# hybrid_lower_pcb3.net
KiCad netlist of a schematic drawn in EAGLE
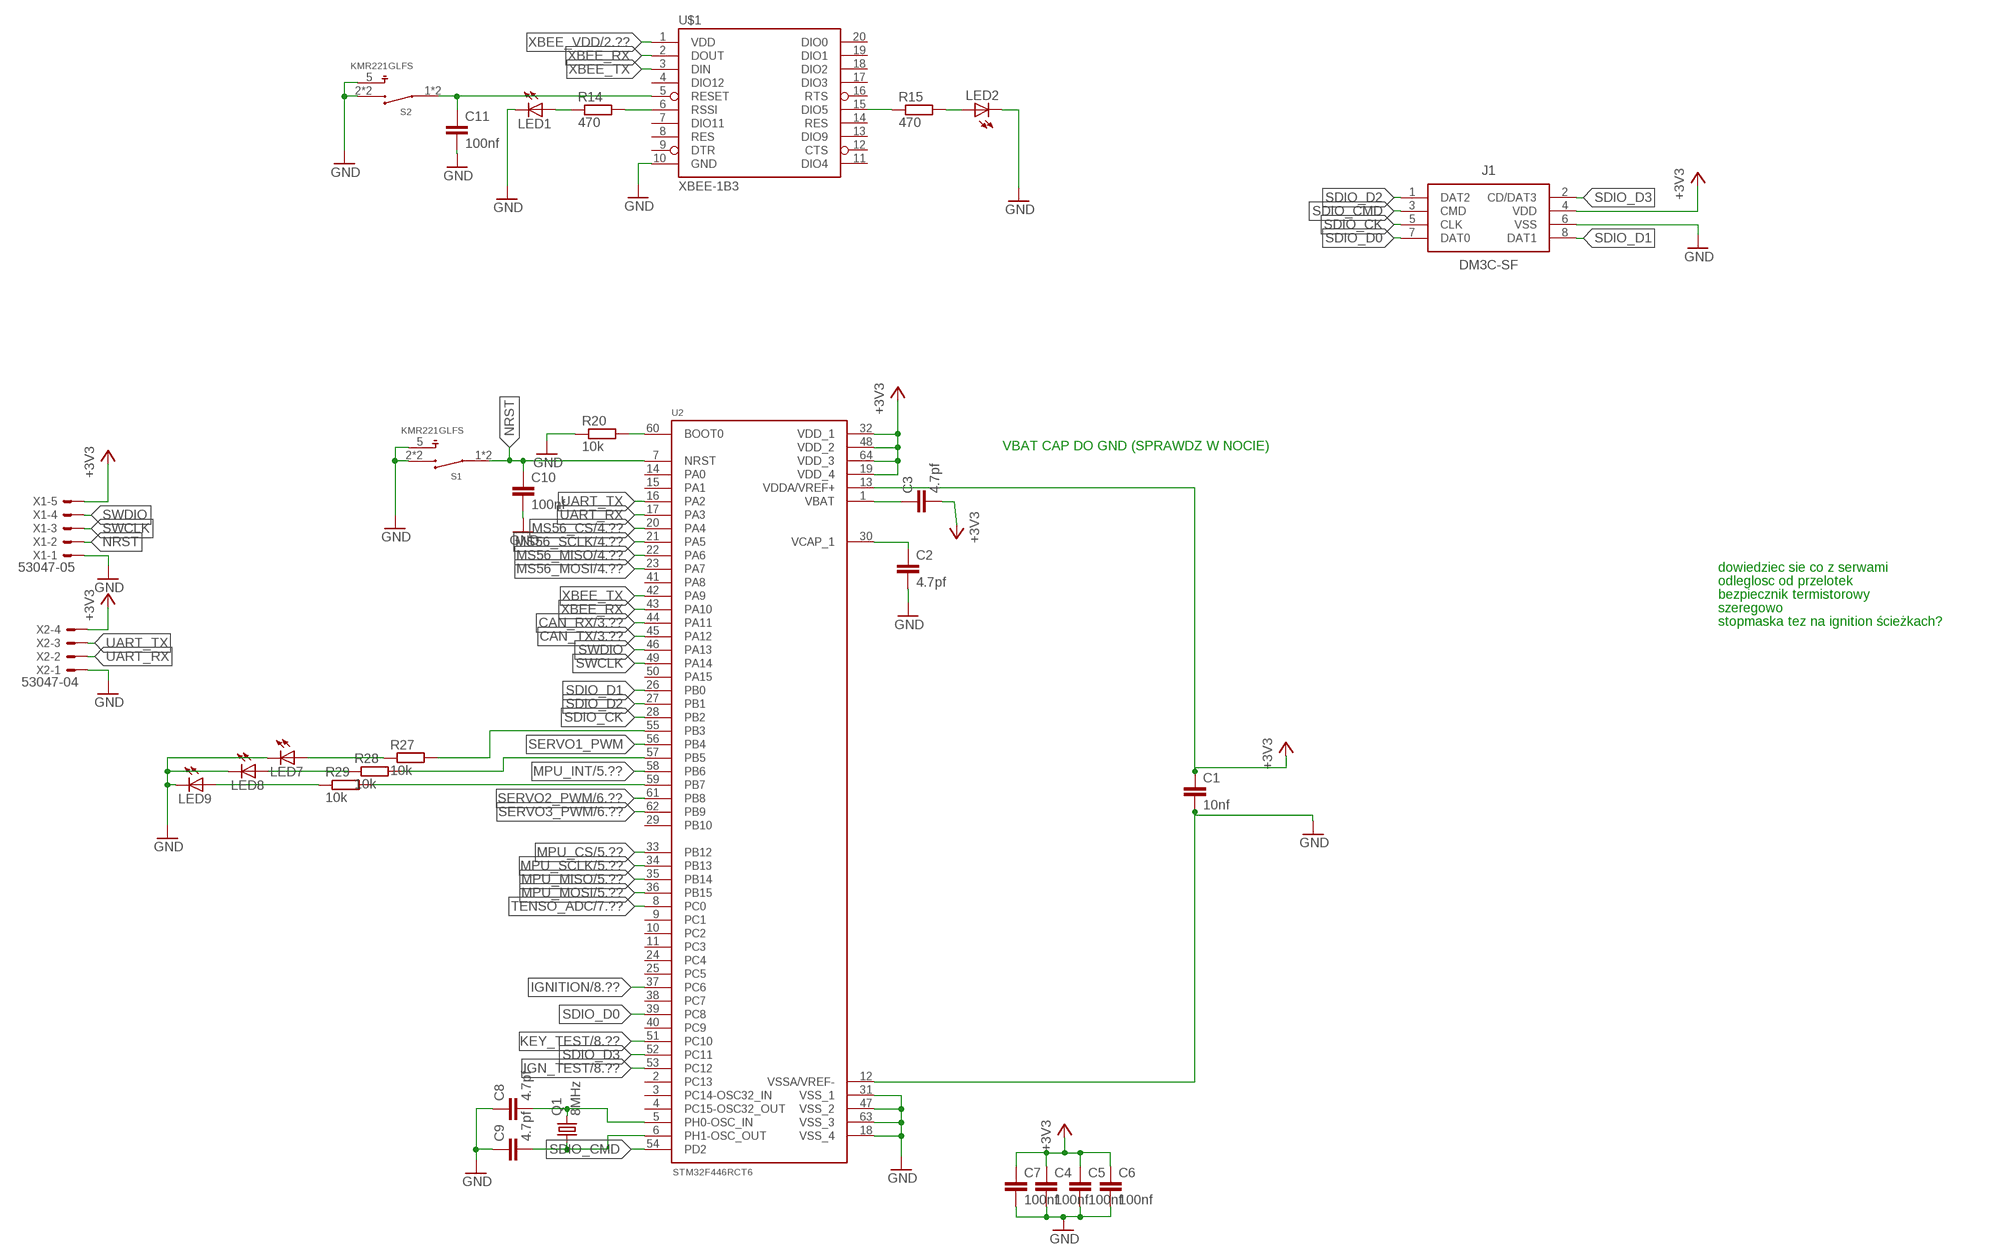
[diagram p0: schematic, sheet 1]
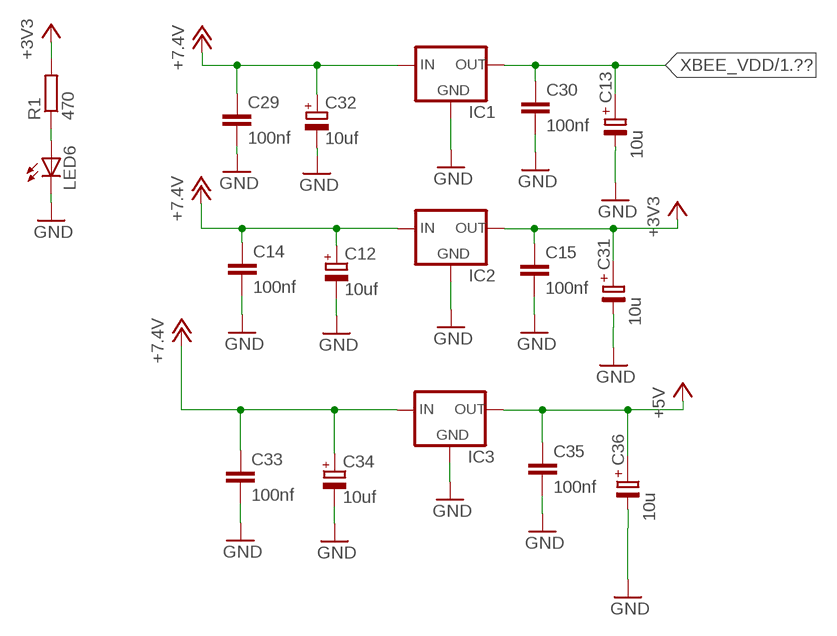
[diagram p1: schematic, sheet 2]
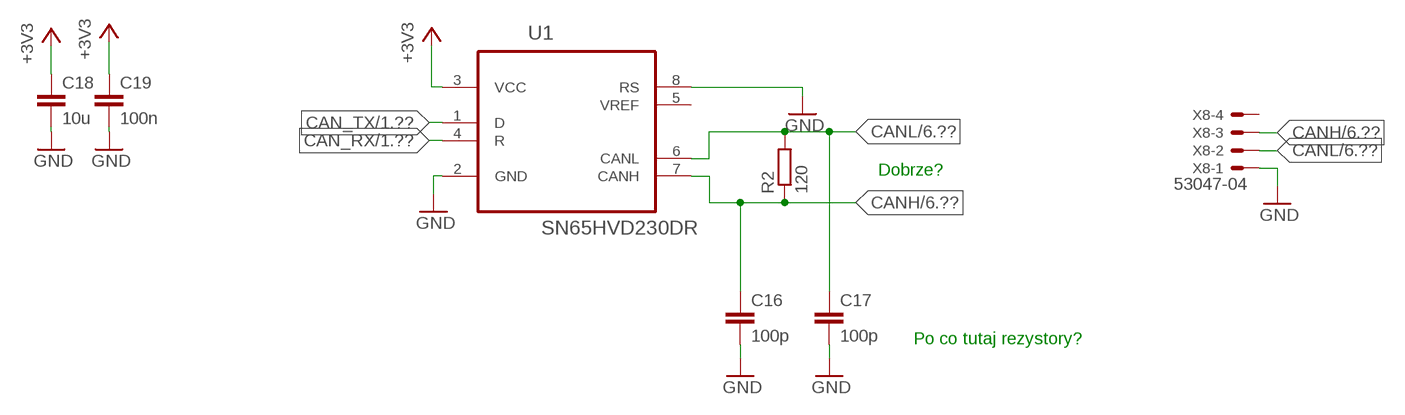
[diagram p2: schematic, sheet 3]
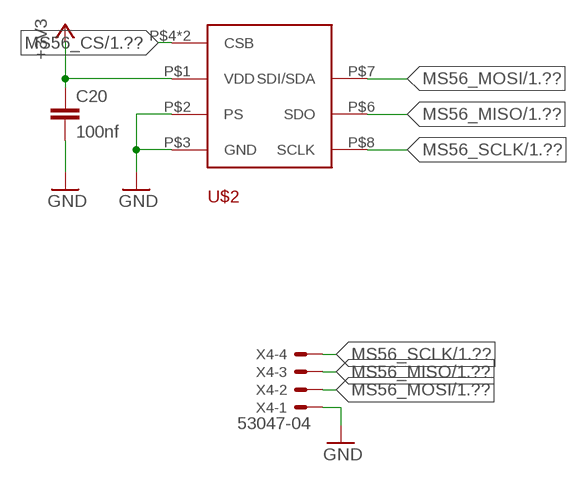
[diagram p3: schematic, sheet 4]
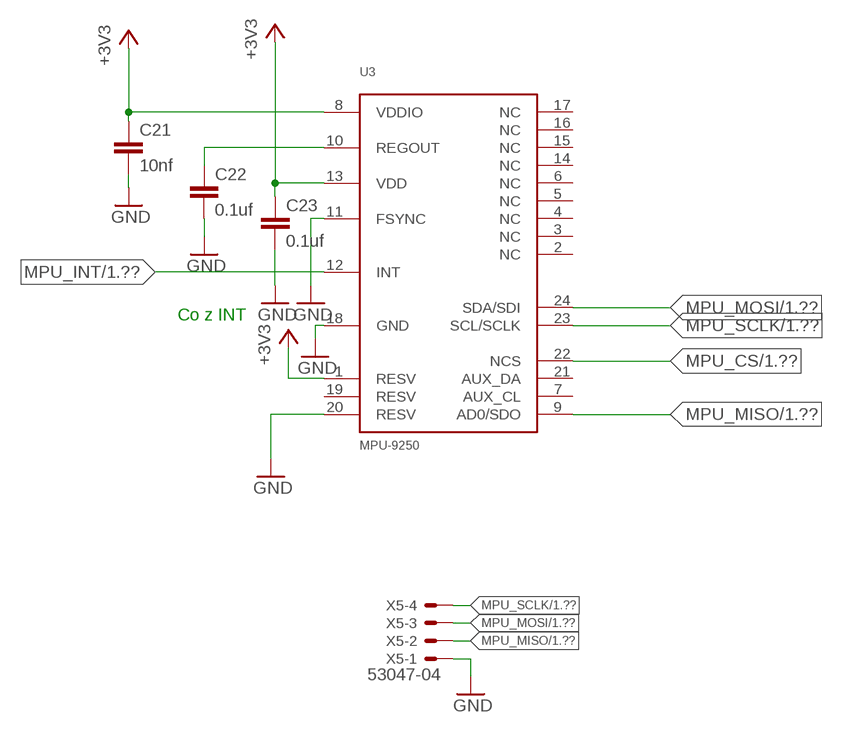
[diagram p4: schematic, sheet 5]
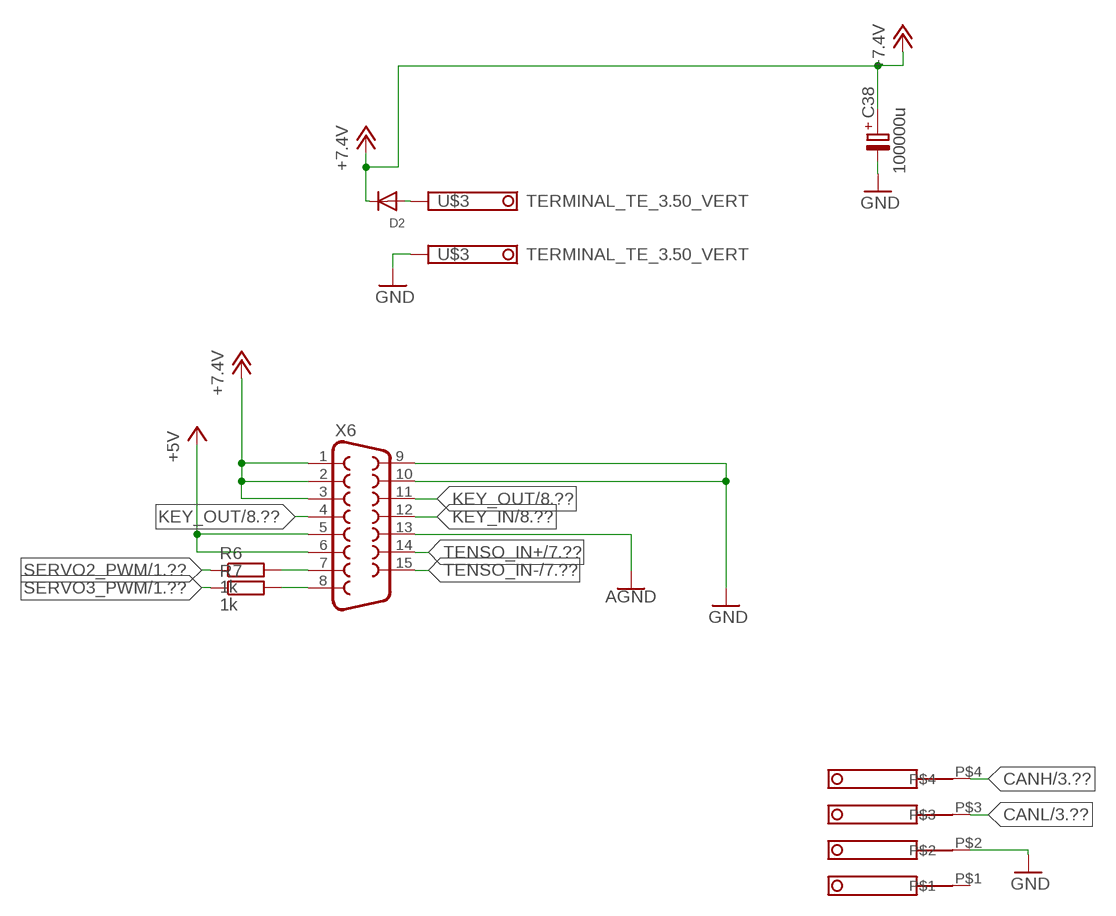
[diagram p5: schematic, sheet 6]
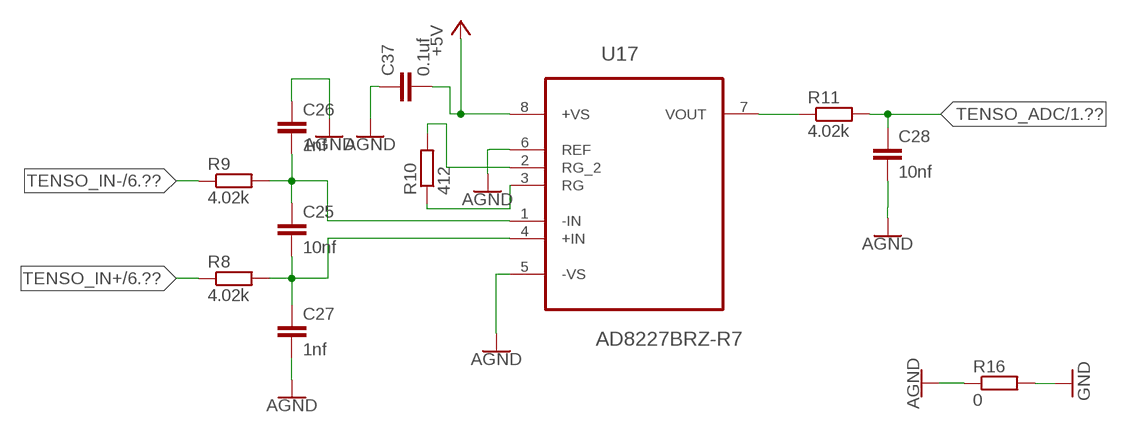
[diagram p6: schematic, sheet 7]
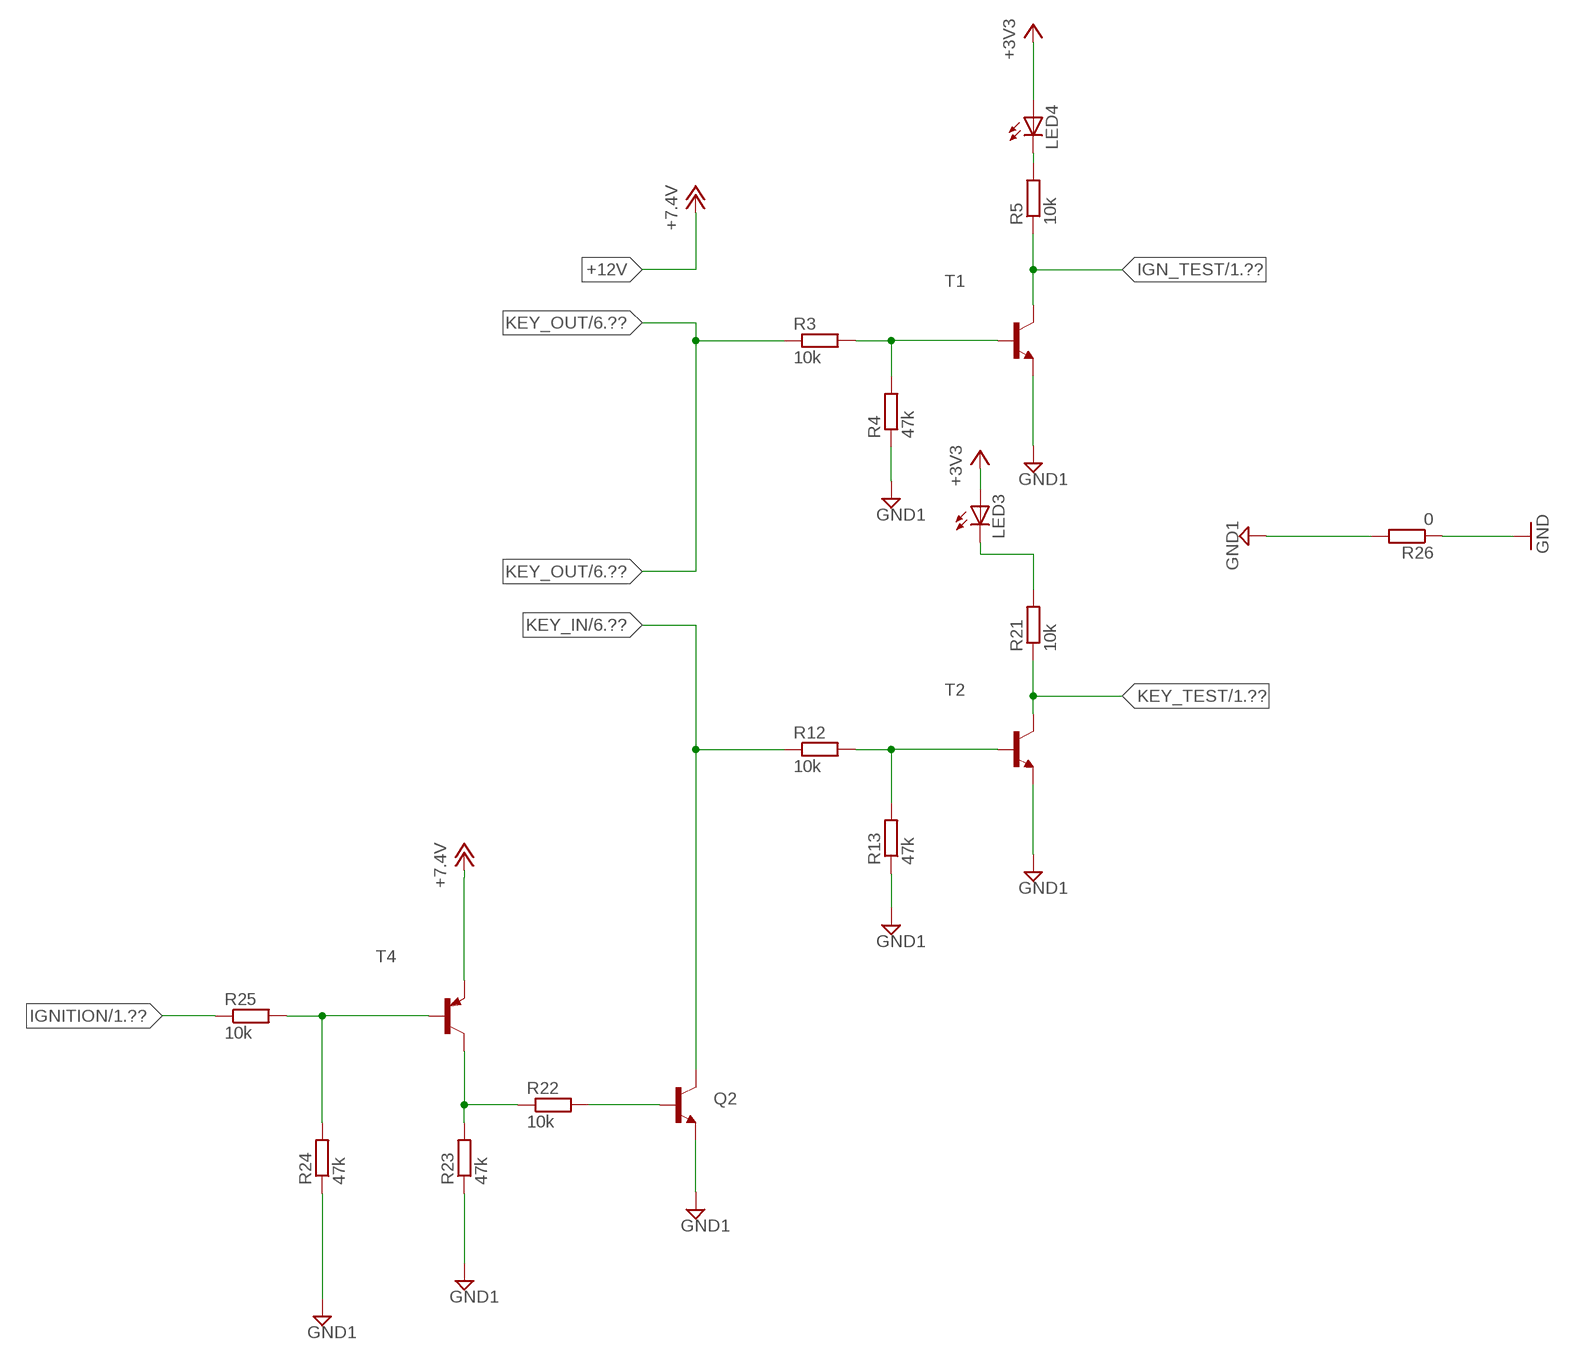
[diagram p7: schematic, sheet 8]

(export (version "E")
  (design (tool "Eeschema 10.0.6"))
  (components
    (comp (ref "C16")
      (value "100p")
      (footprint "eagle-import:C0603")
      (libsource (lib "eagle-import") (part "C-EUC0603"))
    )
    (comp (ref "C17")
      (value "100p")
      (footprint "eagle-import:C0603")
      (libsource (lib "eagle-import") (part "C-EUC0603"))
    )
    (comp (ref "C18")
      (value "10u")
      (footprint "eagle-import:C0603")
      (libsource (lib "eagle-import") (part "C-EUC0603"))
    )
    (comp (ref "C19")
      (value "100n")
      (footprint "eagle-import:C0603")
      (libsource (lib "eagle-import") (part "C-EUC0603"))
    )
    (comp (ref "R2")
      (value "120")
      (footprint "eagle-import:R0603")
      (libsource (lib "eagle-import") (part "R-EU_R0603"))
    )
    (comp (ref "U1")
      (value "SN65HVD230DR")
      (footprint "eagle-import:SOIC127P600X175-8N")
      (fields (field (name "MF") "Texas Instruments"))
      (libsource (lib "eagle-import") (part "SN65HVD230DR"))
    )
    (comp (ref "X8")
      (value "53047-04")
      (footprint "eagle-import:53047-04")
      (fields (field (name "MF") "WALDOM/MOLEX") (field (name "MPN") "53047-0410"))
      (libsource (lib "eagle-import") (part "53?-04047"))
    )
    (comp (ref "C12")
      (value "10uf")
      (footprint "eagle-import:SANYO-OSCON_SMD_B6")
      (libsource (lib "eagle-import") (part "CPOL-EUSANYO_SMD_B6"))
    )
    (comp (ref "C13")
      (value "10u")
      (footprint "eagle-import:TE-B-3528")
      (libsource (lib "eagle-import") (part "C-PR-SMD-TE-B"))
    )
    (comp (ref "C14")
      (value "100nf")
      (footprint "eagle-import:C0603")
      (libsource (lib "eagle-import") (part "C-EUC0603"))
    )
    (comp (ref "C15")
      (value "100nf")
      (footprint "eagle-import:C0603")
      (libsource (lib "eagle-import") (part "C-EUC0603"))
    )
    (comp (ref "C29")
      (value "100nf")
      (footprint "eagle-import:C0603")
      (libsource (lib "eagle-import") (part "C-EUC0603"))
    )
    (comp (ref "C30")
      (value "100nf")
      (footprint "eagle-import:C0603")
      (libsource (lib "eagle-import") (part "C-EUC0603"))
    )
    (comp (ref "C31")
      (value "10u")
      (footprint "eagle-import:TE-B-3528")
      (libsource (lib "eagle-import") (part "C-PR-SMD-TE-B"))
    )
    (comp (ref "C32")
      (value "10uf")
      (footprint "eagle-import:SANYO-OSCON_SMD_B6")
      (libsource (lib "eagle-import") (part "CPOL-EUSANYO_SMD_B6"))
    )
    (comp (ref "C33")
      (value "100nf")
      (footprint "eagle-import:C0603")
      (libsource (lib "eagle-import") (part "C-EUC0603"))
    )
    (comp (ref "C34")
      (value "10uf")
      (footprint "eagle-import:SANYO-OSCON_SMD_B6")
      (libsource (lib "eagle-import") (part "CPOL-EUSANYO_SMD_B6"))
    )
    (comp (ref "C35")
      (value "100nf")
      (footprint "eagle-import:C0603")
      (libsource (lib "eagle-import") (part "C-EUC0603"))
    )
    (comp (ref "C36")
      (value "10u")
      (footprint "eagle-import:TE-B-3528")
      (libsource (lib "eagle-import") (part "C-PR-SMD-TE-B"))
    )
    (comp (ref "IC1")
      (value "LM1117")
      (footprint "eagle-import:SOT223")
      (libsource (lib "eagle-import") (part "LM1117"))
    )
    (comp (ref "IC2")
      (value "LM1117")
      (footprint "eagle-import:SOT223")
      (libsource (lib "eagle-import") (part "LM1117"))
    )
    (comp (ref "IC3")
      (value "LM1117")
      (footprint "eagle-import:SOT223")
      (libsource (lib "eagle-import") (part "LM1117"))
    )
    (comp (ref "LED6")
      (value "LED0603")
      (footprint "eagle-import:LED-0603")
      (libsource (lib "eagle-import") (part "LED0603"))
    )
    (comp (ref "R1")
      (value "470")
      (footprint "eagle-import:R0603")
      (libsource (lib "eagle-import") (part "resistor_348_R-EU_R0603"))
    )
    (comp (ref "C1")
      (value "10nf")
      (footprint "eagle-import:C0603")
      (libsource (lib "eagle-import") (part "C-EUC0603"))
    )
    (comp (ref "C2")
      (value "4.7pf")
      (footprint "eagle-import:C0603")
      (libsource (lib "eagle-import") (part "C-EUC0603"))
    )
    (comp (ref "C3")
      (value "4.7pf")
      (footprint "eagle-import:C0603")
      (libsource (lib "eagle-import") (part "C-EUC0603"))
    )
    (comp (ref "C4")
      (value "100nf")
      (footprint "eagle-import:C0603")
      (libsource (lib "eagle-import") (part "C-EUC0603"))
    )
    (comp (ref "C5")
      (value "100nf")
      (footprint "eagle-import:C0603")
      (libsource (lib "eagle-import") (part "C-EUC0603"))
    )
    (comp (ref "C6")
      (value "100nf")
      (footprint "eagle-import:C0603")
      (libsource (lib "eagle-import") (part "C-EUC0603"))
    )
    (comp (ref "C7")
      (value "100nf")
      (footprint "eagle-import:C0603")
      (libsource (lib "eagle-import") (part "C-EUC0603"))
    )
    (comp (ref "C8")
      (value "4.7pf")
      (footprint "eagle-import:C0603")
      (libsource (lib "eagle-import") (part "C-EUC0603"))
    )
    (comp (ref "C9")
      (value "4.7pf")
      (footprint "eagle-import:C0603")
      (libsource (lib "eagle-import") (part "C-EUC0603"))
    )
    (comp (ref "C10")
      (value "100nf")
      (footprint "eagle-import:C0603")
      (libsource (lib "eagle-import") (part "C-EUC0603"))
    )
    (comp (ref "C11")
      (value "100nf")
      (footprint "eagle-import:C0603")
      (libsource (lib "eagle-import") (part "C-EUC0603"))
    )
    (comp (ref "J1")
      (value "DM3C-SF")
      (footprint "eagle-import:DM3C-SF")
      (fields (field (name "DIGIKEY_PART_NUMBER") "HR1940TR-ND"))
      (libsource (lib "eagle-import") (part "DM3C-SF"))
    )
    (comp (ref "LED1")
      (value "LED0603")
      (footprint "eagle-import:LED-0603")
      (libsource (lib "eagle-import") (part "LED0603"))
    )
    (comp (ref "LED2")
      (value "LED0603")
      (footprint "eagle-import:LED-0603")
      (libsource (lib "eagle-import") (part "LED0603"))
    )
    (comp (ref "LED7")
      (value "LED0603")
      (footprint "eagle-import:LED-0603")
      (libsource (lib "eagle-import") (part "LED0603"))
    )
    (comp (ref "LED8")
      (value "LED0603")
      (footprint "eagle-import:LED-0603")
      (libsource (lib "eagle-import") (part "LED0603"))
    )
    (comp (ref "LED9")
      (value "LED0603")
      (footprint "eagle-import:LED-0603")
      (libsource (lib "eagle-import") (part "LED0603"))
    )
    (comp (ref "Q1")
      (value "8MHz")
      (footprint "eagle-import:CTS406")
      (libsource (lib "eagle-import") (part "CRYSTALCTS406"))
    )
    (comp (ref "R14")
      (value "470")
      (footprint "eagle-import:R0603")
      (libsource (lib "eagle-import") (part "R-EU_R0603"))
    )
    (comp (ref "R15")
      (value "470")
      (footprint "eagle-import:R0603")
      (libsource (lib "eagle-import") (part "R-EU_R0603"))
    )
    (comp (ref "R20")
      (value "10k")
      (footprint "eagle-import:R0603")
      (libsource (lib "eagle-import") (part "resistor_348_R-EU_R0603"))
    )
    (comp (ref "R27")
      (value "10k")
      (footprint "eagle-import:R0603")
      (libsource (lib "eagle-import") (part "resistor_348_R-EU_R0603"))
    )
    (comp (ref "R28")
      (value "10k")
      (footprint "eagle-import:R0603")
      (libsource (lib "eagle-import") (part "resistor_348_R-EU_R0603"))
    )
    (comp (ref "R29")
      (value "10k")
      (footprint "eagle-import:R0603")
      (libsource (lib "eagle-import") (part "resistor_348_R-EU_R0603"))
    )
    (comp (ref "S1")
      (value "KMR221GLFS")
      (footprint "eagle-import:SW_KMR221GLFS")
      (fields (field (name "MF") "C&K Components"))
      (libsource (lib "eagle-import") (part "KMR221GLFS"))
    )
    (comp (ref "S2")
      (value "KMR221GLFS")
      (footprint "eagle-import:SW_KMR221GLFS")
      (fields (field (name "MF") "C&K Components"))
      (libsource (lib "eagle-import") (part "KMR221GLFS"))
    )
    (comp (ref "U$1")
      (value "XBEE-1B3")
      (footprint "eagle-import:XBEE-SMD")
      (libsource (lib "eagle-import") (part "XBEE-1B3"))
    )
    (comp (ref "U2")
      (value "STM32F446RCT6")
      (footprint "eagle-import:QFP50P1200X1200X160-64N")
      (fields (field (name "MF") "STMicroelectronics"))
      (libsource (lib "eagle-import") (part "STM32F446RCT6"))
    )
    (comp (ref "X1")
      (value "53047-05")
      (footprint "eagle-import:53047-05")
      (fields (field (name "MF") "MOLEX") (field (name "MPN") "53047-0510"))
      (libsource (lib "eagle-import") (part "53?-05047"))
    )
    (comp (ref "X2")
      (value "53047-04")
      (footprint "eagle-import:53047-04")
      (fields (field (name "MF") "WALDOM/MOLEX") (field (name "MPN") "53047-0410"))
      (libsource (lib "eagle-import") (part "53?-04047"))
    )
    (comp (ref "C25")
      (value "10nf")
      (footprint "eagle-import:C0603")
      (libsource (lib "eagle-import") (part "C-EUC0603"))
    )
    (comp (ref "C26")
      (value "1nf")
      (footprint "eagle-import:C0603")
      (libsource (lib "eagle-import") (part "C-EUC0603"))
    )
    (comp (ref "C27")
      (value "1nf")
      (footprint "eagle-import:C0603")
      (libsource (lib "eagle-import") (part "C-EUC0603"))
    )
    (comp (ref "C28")
      (value "10nf")
      (footprint "eagle-import:C0603")
      (libsource (lib "eagle-import") (part "C-EUC0603"))
    )
    (comp (ref "C37")
      (value "0.1uf")
      (footprint "eagle-import:C0603")
      (libsource (lib "eagle-import") (part "C-EUC0603"))
    )
    (comp (ref "R8")
      (value "4.02k")
      (footprint "eagle-import:R0603")
      (libsource (lib "eagle-import") (part "R-EU_R0603"))
    )
    (comp (ref "R9")
      (value "4.02k")
      (footprint "eagle-import:R0603")
      (libsource (lib "eagle-import") (part "R-EU_R0603"))
    )
    (comp (ref "R10")
      (value "412")
      (footprint "eagle-import:R0805")
      (libsource (lib "eagle-import") (part "R-EU_R0805"))
    )
    (comp (ref "R11")
      (value "4.02k")
      (footprint "eagle-import:R0603")
      (libsource (lib "eagle-import") (part "R-EU_R0603"))
    )
    (comp (ref "R16")
      (value "0")
      (footprint "eagle-import:R0603")
      (libsource (lib "eagle-import") (part "resistor_348_R-EU_R0603"))
    )
    (comp (ref "U17")
      (value "AD8227BRZ-R7")
      (footprint "eagle-import:SOIC127P600X175-8N")
      (libsource (lib "eagle-import") (part "AD8227BRZ-R7"))
    )
    (comp (ref "C38")
      (value "100000u")
      (footprint "eagle-import:TE-B-3528")
      (libsource (lib "eagle-import") (part "C-PR-SMD-TE-B"))
    )
    (comp (ref "D2")
      (value "DIODESOD-523")
      (footprint "eagle-import:SOD-523")
      (libsource (lib "eagle-import") (part "DIODESOD-523"))
    )
    (comp (ref "R6")
      (value "1k")
      (footprint "eagle-import:R0603")
      (libsource (lib "eagle-import") (part "R-EU_R0603"))
    )
    (comp (ref "R7")
      (value "1k")
      (footprint "eagle-import:R0603")
      (libsource (lib "eagle-import") (part "R-EU_R0603"))
    )
    (comp (ref "U$3")
      (value "TERMINAL_TE_3.50_VERT")
      (footprint "eagle-import:TE_3.5_TERMINAL_VERT")
      (libsource (lib "eagle-import") (part "TERMINAL_TE_3.50_VERT"))
    )
    (comp (ref "U$10")
      (value "39505-1005")
      (footprint "eagle-import:39505-1005")
      (libsource (lib "eagle-import") (part "39505-1005"))
    )
    (comp (ref "X6")
      (value "F15VP")
      (footprint "eagle-import:F15VP")
      (libsource (lib "eagle-import") (part "F15VP"))
    )
    (comp (ref "LED3")
      (value "LED0603")
      (footprint "eagle-import:LED-0603")
      (libsource (lib "eagle-import") (part "LED0603"))
    )
    (comp (ref "LED4")
      (value "LED0603")
      (footprint "eagle-import:LED-0603")
      (libsource (lib "eagle-import") (part "LED0603"))
    )
    (comp (ref "Q2")
      (value "TRANSISTOR_NPNSOT23-3")
      (footprint "eagle-import:SOT23-3")
      (libsource (lib "eagle-import") (part "TRANSISTOR_NPNSOT23-3"))
    )
    (comp (ref "R3")
      (value "10k")
      (footprint "eagle-import:R0603")
      (libsource (lib "eagle-import") (part "R-EU_R0603"))
    )
    (comp (ref "R4")
      (value "47k")
      (footprint "eagle-import:R0603")
      (libsource (lib "eagle-import") (part "R-EU_R0603"))
    )
    (comp (ref "R5")
      (value "10k")
      (footprint "eagle-import:R0603")
      (libsource (lib "eagle-import") (part "R-EU_R0603"))
    )
    (comp (ref "R12")
      (value "10k")
      (footprint "eagle-import:R0603")
      (libsource (lib "eagle-import") (part "R-EU_R0603"))
    )
    (comp (ref "R13")
      (value "47k")
      (footprint "eagle-import:R0603")
      (libsource (lib "eagle-import") (part "R-EU_R0603"))
    )
    (comp (ref "R21")
      (value "10k")
      (footprint "eagle-import:R0603")
      (libsource (lib "eagle-import") (part "R-EU_R0603"))
    )
    (comp (ref "R22")
      (value "10k")
      (footprint "eagle-import:R0603")
      (libsource (lib "eagle-import") (part "R-EU_R0603"))
    )
    (comp (ref "R23")
      (value "47k")
      (footprint "eagle-import:R0603")
      (libsource (lib "eagle-import") (part "R-EU_R0603"))
    )
    (comp (ref "R24")
      (value "47k")
      (footprint "eagle-import:R0603")
      (libsource (lib "eagle-import") (part "R-EU_R0603"))
    )
    (comp (ref "R25")
      (value "10k")
      (footprint "eagle-import:R0603")
      (libsource (lib "eagle-import") (part "R-EU_R0603"))
    )
    (comp (ref "R26")
      (value "0")
      (footprint "eagle-import:R0603")
      (libsource (lib "eagle-import") (part "R-EU_R0603"))
    )
    (comp (ref "T1")
      (value "BCW81-NPN-SOT23-BEC")
      (footprint "eagle-import:SOT23-BEC")
      (libsource (lib "eagle-import") (part "-NPN-SOT23-BECBCW81"))
    )
    (comp (ref "T2")
      (value "BCW81-NPN-SOT23-BEC")
      (footprint "eagle-import:SOT23-BEC")
      (libsource (lib "eagle-import") (part "-NPN-SOT23-BECBCW81"))
    )
    (comp (ref "T4")
      (value "BC807-16-PNP-SOT23-BEC")
      (footprint "eagle-import:SOT23-BEC")
      (libsource (lib "eagle-import") (part "-PNP-SOT23-BECBC807-16"))
    )
    (comp (ref "C20")
      (value "100nf")
      (footprint "eagle-import:C0603")
      (libsource (lib "eagle-import") (part "resistor_348_C-EUC0603"))
    )
    (comp (ref "U$2")
      (value "MS56XX")
      (footprint "eagle-import:MS56XX")
      (libsource (lib "eagle-import") (part "MS56XX"))
    )
    (comp (ref "X4")
      (value "53047-04")
      (footprint "eagle-import:53047-04")
      (fields (field (name "MF") "WALDOM/MOLEX") (field (name "MPN") "53047-0410"))
      (libsource (lib "eagle-import") (part "53?-04047"))
    )
    (comp (ref "C21")
      (value "10nf")
      (footprint "eagle-import:C0603")
      (libsource (lib "eagle-import") (part "C-EUC0603"))
    )
    (comp (ref "C22")
      (value "0.1uf")
      (footprint "eagle-import:C0603")
      (libsource (lib "eagle-import") (part "C-EUC0603"))
    )
    (comp (ref "C23")
      (value "0.1uf")
      (footprint "eagle-import:C0603")
      (libsource (lib "eagle-import") (part "C-EUC0603"))
    )
    (comp (ref "U3")
      (value "MPU-9250")
      (footprint "eagle-import:MPU-9250")
      (fields (field (name "MF") "InvenSense"))
      (libsource (lib "eagle-import") (part "MPU-9250"))
    )
    (comp (ref "X5")
      (value "53047-04")
      (footprint "eagle-import:53047-04")
      (fields (field (name "MF") "WALDOM/MOLEX") (field (name "MPN") "53047-0410"))
      (libsource (lib "eagle-import") (part "53?-04047"))
    )
  )
  (nets
    (net (code "1") (name "+3V3") (class "Default")
      (node (ref "C1") (pin "1") (pinfunction "1_1") (pintype "passive"))
      (node (ref "C15") (pin "1") (pinfunction "1_1") (pintype "passive"))
      (node (ref "C18") (pin "1") (pinfunction "1_1") (pintype "passive"))
      (node (ref "C19") (pin "1") (pinfunction "1_1") (pintype "passive"))
      (node (ref "C20") (pin "1") (pinfunction "1_1") (pintype "passive"))
      (node (ref "C21") (pin "1") (pinfunction "1_1") (pintype "passive"))
      (node (ref "C23") (pin "1") (pinfunction "1_1") (pintype "passive"))
      (node (ref "C3") (pin "2") (pinfunction "2_2") (pintype "passive"))
      (node (ref "C31") (pin "+") (pinfunction "+_+") (pintype "passive"))
      (node (ref "C4") (pin "1") (pinfunction "1_1") (pintype "passive"))
      (node (ref "C5") (pin "1") (pinfunction "1_1") (pintype "passive"))
      (node (ref "C6") (pin "1") (pinfunction "1_1") (pintype "passive"))
      (node (ref "C7") (pin "1") (pinfunction "1_1") (pintype "passive"))
      (node (ref "IC2") (pin "2") (pinfunction "OUT_2") (pintype "passive"))
      (node (ref "J1") (pin "4") (pinfunction "VDD_4") (pintype "passive"))
      (node (ref "LED3") (pin "A") (pinfunction "A_A") (pintype "passive"))
      (node (ref "LED4") (pin "A") (pinfunction "A_A") (pintype "passive"))
      (node (ref "R1") (pin "2") (pinfunction "2_2") (pintype "passive"))
      (node (ref "U$2") (pin "P$1") (pinfunction "VDD_P$1") (pintype "bidirectional"))
      (node (ref "U1") (pin "3") (pinfunction "VCC_3") (pintype "power_in"))
      (node (ref "U2") (pin "13") (pinfunction "VDDA/VREF+_13") (pintype "power_in"))
      (node (ref "U2") (pin "19") (pinfunction "VDD_4_19") (pintype "power_in"))
      (node (ref "U2") (pin "32") (pinfunction "VDD_1_32") (pintype "power_in"))
      (node (ref "U2") (pin "48") (pinfunction "VDD_2_48") (pintype "power_in"))
      (node (ref "U2") (pin "64") (pinfunction "VDD_3_64") (pintype "power_in"))
      (node (ref "U3") (pin "1") (pinfunction "RESV_1") (pintype "bidirectional"))
      (node (ref "U3") (pin "13") (pinfunction "VDD_13") (pintype "bidirectional"))
      (node (ref "U3") (pin "8") (pinfunction "VDDIO_8") (pintype "bidirectional"))
      (node (ref "X1") (pin "5") (pinfunction "S_5") (pintype "passive"))
      (node (ref "X2") (pin "4") (pinfunction "S_4") (pintype "passive"))
    )
    (net (code "2") (name "+5V") (class "Default")
      (node (ref "C35") (pin "1") (pinfunction "1_1") (pintype "passive"))
      (node (ref "C36") (pin "+") (pinfunction "+_+") (pintype "passive"))
      (node (ref "C37") (pin "2") (pinfunction "2_2") (pintype "passive"))
      (node (ref "IC3") (pin "2") (pinfunction "OUT_2") (pintype "passive"))
      (node (ref "U17") (pin "8") (pinfunction "+VS_8") (pintype "power_in"))
      (node (ref "X6") (pin "5") (pinfunction "5_5") (pintype "passive"))
      (node (ref "X6") (pin "6") (pinfunction "6_6") (pintype "passive"))
    )
    (net (code "3") (name "+12V") (class "Default")
      (node (ref "C12") (pin "+") (pinfunction "+_+") (pintype "passive"))
      (node (ref "C14") (pin "1") (pinfunction "1_1") (pintype "passive"))
      (node (ref "C29") (pin "1") (pinfunction "1_1") (pintype "passive"))
      (node (ref "C32") (pin "+") (pinfunction "+_+") (pintype "passive"))
      (node (ref "C33") (pin "1") (pinfunction "1_1") (pintype "passive"))
      (node (ref "C34") (pin "+") (pinfunction "+_+") (pintype "passive"))
      (node (ref "C38") (pin "+") (pinfunction "+_+") (pintype "passive"))
      (node (ref "D2") (pin "K") (pinfunction "C_K") (pintype "passive"))
      (node (ref "IC1") (pin "3") (pinfunction "IN_3") (pintype "input"))
      (node (ref "IC2") (pin "3") (pinfunction "IN_3") (pintype "input"))
      (node (ref "IC3") (pin "3") (pinfunction "IN_3") (pintype "input"))
      (node (ref "T4") (pin "E") (pinfunction "E_E") (pintype "passive"))
      (node (ref "X6") (pin "1") (pinfunction "1_1") (pintype "passive"))
      (node (ref "X6") (pin "2") (pinfunction "2_2") (pintype "passive"))
      (node (ref "X6") (pin "3") (pinfunction "3_3") (pintype "passive"))
    )
    (net (code "4") (name "AGND") (class "Default")
      (node (ref "C26") (pin "1") (pinfunction "1_1") (pintype "passive"))
      (node (ref "C27") (pin "2") (pinfunction "2_2") (pintype "passive"))
      (node (ref "C28") (pin "2") (pinfunction "2_2") (pintype "passive"))
      (node (ref "C37") (pin "1") (pinfunction "1_1") (pintype "passive"))
      (node (ref "R16") (pin "1") (pinfunction "1_1") (pintype "passive"))
      (node (ref "U17") (pin "5") (pinfunction "-VS_5") (pintype "power_in"))
      (node (ref "U17") (pin "6") (pinfunction "REF_6") (pintype "input"))
      (node (ref "X6") (pin "13") (pinfunction "13_13") (pintype "passive"))
    )
    (net (code "5") (name "CANH") (class "Default")
      (node (ref "C16") (pin "1") (pinfunction "1_1") (pintype "passive"))
      (node (ref "R2") (pin "1") (pinfunction "1_1") (pintype "passive"))
      (node (ref "U$10") (pin "P$4") (pinfunction "P$4_P$4") (pintype "bidirectional"))
      (node (ref "U1") (pin "7") (pinfunction "CANH_7") (pintype "output"))
      (node (ref "X8") (pin "3") (pinfunction "S_3") (pintype "passive"))
    )
    (net (code "6") (name "CANL") (class "Default")
      (node (ref "C17") (pin "1") (pinfunction "1_1") (pintype "passive"))
      (node (ref "R2") (pin "2") (pinfunction "2_2") (pintype "passive"))
      (node (ref "U$10") (pin "P$3") (pinfunction "P$3_P$3") (pintype "bidirectional"))
      (node (ref "U1") (pin "6") (pinfunction "CANL_6") (pintype "output"))
      (node (ref "X8") (pin "2") (pinfunction "S_2") (pintype "passive"))
    )
    (net (code "7") (name "CAN_RX") (class "Default")
      (node (ref "U1") (pin "4") (pinfunction "R_4") (pintype "output"))
      (node (ref "U2") (pin "44") (pinfunction "PA11_44") (pintype "bidirectional"))
    )
    (net (code "8") (name "CAN_TX") (class "Default")
      (node (ref "U1") (pin "1") (pinfunction "D_1") (pintype "input"))
      (node (ref "U2") (pin "45") (pinfunction "PA12_45") (pintype "bidirectional"))
    )
    (net (code "9") (name "GND") (class "Default")
      (node (ref "C1") (pin "2") (pinfunction "2_2") (pintype "passive"))
      (node (ref "C10") (pin "2") (pinfunction "2_2") (pintype "passive"))
      (node (ref "C11") (pin "2") (pinfunction "2_2") (pintype "passive"))
      (node (ref "C12") (pin "-") (pinfunction "-_-") (pintype "passive"))
      (node (ref "C13") (pin "-") (pinfunction "-_-") (pintype "passive"))
      (node (ref "C14") (pin "2") (pinfunction "2_2") (pintype "passive"))
      (node (ref "C15") (pin "2") (pinfunction "2_2") (pintype "passive"))
      (node (ref "C16") (pin "2") (pinfunction "2_2") (pintype "passive"))
      (node (ref "C17") (pin "2") (pinfunction "2_2") (pintype "passive"))
      (node (ref "C18") (pin "2") (pinfunction "2_2") (pintype "passive"))
      (node (ref "C19") (pin "2") (pinfunction "2_2") (pintype "passive"))
      (node (ref "C2") (pin "2") (pinfunction "2_2") (pintype "passive"))
      (node (ref "C20") (pin "2") (pinfunction "2_2") (pintype "passive"))
      (node (ref "C21") (pin "2") (pinfunction "2_2") (pintype "passive"))
      (node (ref "C22") (pin "2") (pinfunction "2_2") (pintype "passive"))
      (node (ref "C23") (pin "2") (pinfunction "2_2") (pintype "passive"))
      (node (ref "C29") (pin "2") (pinfunction "2_2") (pintype "passive"))
      (node (ref "C30") (pin "2") (pinfunction "2_2") (pintype "passive"))
      (node (ref "C31") (pin "-") (pinfunction "-_-") (pintype "passive"))
      (node (ref "C32") (pin "-") (pinfunction "-_-") (pintype "passive"))
      (node (ref "C33") (pin "2") (pinfunction "2_2") (pintype "passive"))
      (node (ref "C34") (pin "-") (pinfunction "-_-") (pintype "passive"))
      (node (ref "C35") (pin "2") (pinfunction "2_2") (pintype "passive"))
      (node (ref "C36") (pin "-") (pinfunction "-_-") (pintype "passive"))
      (node (ref "C38") (pin "-") (pinfunction "-_-") (pintype "passive"))
      (node (ref "C4") (pin "2") (pinfunction "2_2") (pintype "passive"))
      (node (ref "C5") (pin "2") (pinfunction "2_2") (pintype "passive"))
      (node (ref "C6") (pin "2") (pinfunction "2_2") (pintype "passive"))
      (node (ref "C7") (pin "2") (pinfunction "2_2") (pintype "passive"))
      (node (ref "C8") (pin "1") (pinfunction "1_1") (pintype "passive"))
      (node (ref "C9") (pin "1") (pinfunction "1_1") (pintype "passive"))
      (node (ref "IC1") (pin "1") (pinfunction "GND_1") (pintype "input"))
      (node (ref "IC2") (pin "1") (pinfunction "GND_1") (pintype "input"))
      (node (ref "IC3") (pin "1") (pinfunction "GND_1") (pintype "input"))
      (node (ref "J1") (pin "6") (pinfunction "VSS_6") (pintype "passive"))
      (node (ref "LED1") (pin "C") (pinfunction "C_C") (pintype "passive"))
      (node (ref "LED2") (pin "C") (pinfunction "C_C") (pintype "passive"))
      (node (ref "LED6") (pin "C") (pinfunction "C_C") (pintype "passive"))
      (node (ref "LED7") (pin "C") (pinfunction "C_C") (pintype "passive"))
      (node (ref "LED8") (pin "C") (pinfunction "C_C") (pintype "passive"))
      (node (ref "LED9") (pin "C") (pinfunction "C_C") (pintype "passive"))
      (node (ref "R16") (pin "2") (pinfunction "2_2") (pintype "passive"))
      (node (ref "R20") (pin "1") (pinfunction "1_1") (pintype "passive"))
      (node (ref "R26") (pin "1") (pinfunction "1_1") (pintype "passive"))
      (node (ref "S1") (pin "2") (pinfunction "3_2") (pintype "passive"))
      (node (ref "S1") (pin "3") (pinfunction "3_3") (pintype "passive"))
      (node (ref "S1") (pin "5") (pinfunction "5_5") (pintype "passive"))
      (node (ref "S2") (pin "2") (pinfunction "3_2") (pintype "passive"))
      (node (ref "S2") (pin "3") (pinfunction "3_3") (pintype "passive"))
      (node (ref "S2") (pin "5") (pinfunction "5_5") (pintype "passive"))
      (node (ref "U$1") (pin "10") (pinfunction "GND_10") (pintype "power_in"))
      (node (ref "U$10") (pin "P$2") (pinfunction "P$2_P$2") (pintype "bidirectional"))
      (node (ref "U$2") (pin "P$2") (pinfunction "PS_P$2") (pintype "bidirectional"))
      (node (ref "U$2") (pin "P$3") (pinfunction "GND_P$3") (pintype "bidirectional"))
      (node (ref "U$3") (pin "P$2") (pinfunction "K1_P$2") (pintype "passive"))
      (node (ref "U1") (pin "2") (pinfunction "GND_2") (pintype "passive"))
      (node (ref "U1") (pin "8") (pinfunction "RS_8") (pintype "input"))
      (node (ref "U2") (pin "12") (pinfunction "VSSA/VREF-_12") (pintype "power_in"))
      (node (ref "U2") (pin "18") (pinfunction "VSS_4_18") (pintype "power_in"))
      (node (ref "U2") (pin "31") (pinfunction "VSS_1_31") (pintype "power_in"))
      (node (ref "U2") (pin "47") (pinfunction "VSS_2_47") (pintype "power_in"))
      (node (ref "U2") (pin "63") (pinfunction "VSS_3_63") (pintype "power_in"))
      (node (ref "U3") (pin "11") (pinfunction "FSYNC_11") (pintype "bidirectional"))
      (node (ref "U3") (pin "18") (pinfunction "GND_18") (pintype "bidirectional"))
      (node (ref "U3") (pin "20") (pinfunction "RESV_20") (pintype "bidirectional"))
      (node (ref "X1") (pin "1") (pinfunction "S_1") (pintype "passive"))
      (node (ref "X2") (pin "1") (pinfunction "S_1") (pintype "passive"))
      (node (ref "X4") (pin "1") (pinfunction "S_1") (pintype "passive"))
      (node (ref "X5") (pin "1") (pinfunction "S_1") (pintype "passive"))
      (node (ref "X6") (pin "10") (pinfunction "10_10") (pintype "passive"))
      (node (ref "X6") (pin "9") (pinfunction "9_9") (pintype "passive"))
      (node (ref "X8") (pin "1") (pinfunction "S_1") (pintype "passive"))
    )
    (net (code "10") (name "GND1") (class "Default")
      (node (ref "Q2") (pin "2") (pinfunction "E_2") (pintype "passive"))
      (node (ref "R13") (pin "1") (pinfunction "1_1") (pintype "passive"))
      (node (ref "R23") (pin "1") (pinfunction "1_1") (pintype "passive"))
      (node (ref "R24") (pin "1") (pinfunction "1_1") (pintype "passive"))
      (node (ref "R26") (pin "2") (pinfunction "2_2") (pintype "passive"))
      (node (ref "R4") (pin "1") (pinfunction "1_1") (pintype "passive"))
      (node (ref "T1") (pin "E") (pinfunction "E_E") (pintype "passive"))
      (node (ref "T2") (pin "E") (pinfunction "E_E") (pintype "passive"))
    )
    (net (code "11") (name "IGNITION") (class "Default")
      (node (ref "R25") (pin "1") (pinfunction "1_1") (pintype "passive"))
      (node (ref "U2") (pin "37") (pinfunction "PC6_37") (pintype "bidirectional"))
    )
    (net (code "12") (name "IGN_TEST") (class "Default")
      (node (ref "R5") (pin "1") (pinfunction "1_1") (pintype "passive"))
      (node (ref "T1") (pin "C") (pinfunction "C_C") (pintype "passive"))
      (node (ref "U2") (pin "53") (pinfunction "PC12_53") (pintype "bidirectional"))
    )
    (net (code "13") (name "KEY_IN") (class "Default")
      (node (ref "Q2") (pin "3") (pinfunction "C_3") (pintype "passive"))
      (node (ref "R12") (pin "1") (pinfunction "1_1") (pintype "passive"))
      (node (ref "X6") (pin "12") (pinfunction "12_12") (pintype "passive"))
    )
    (net (code "14") (name "KEY_OUT") (class "Default")
      (node (ref "R3") (pin "1") (pinfunction "1_1") (pintype "passive"))
      (node (ref "X6") (pin "11") (pinfunction "11_11") (pintype "passive"))
      (node (ref "X6") (pin "4") (pinfunction "4_4") (pintype "passive"))
    )
    (net (code "15") (name "KEY_TEST") (class "Default")
      (node (ref "R21") (pin "1") (pinfunction "1_1") (pintype "passive"))
      (node (ref "T2") (pin "C") (pinfunction "C_C") (pintype "passive"))
      (node (ref "U2") (pin "51") (pinfunction "PC10_51") (pintype "bidirectional"))
    )
    (net (code "16") (name "MPU_CS") (class "Default")
      (node (ref "U2") (pin "33") (pinfunction "PB12_33") (pintype "bidirectional"))
      (node (ref "U3") (pin "22") (pinfunction "NCS_22") (pintype "bidirectional"))
    )
    (net (code "17") (name "MPU_INT") (class "Default")
      (node (ref "U2") (pin "58") (pinfunction "PB6_58") (pintype "bidirectional"))
      (node (ref "U3") (pin "12") (pinfunction "INT_12") (pintype "bidirectional"))
    )
    (net (code "18") (name "MPU_MISO") (class "Default")
      (node (ref "U2") (pin "35") (pinfunction "PB14_35") (pintype "bidirectional"))
      (node (ref "U3") (pin "9") (pinfunction "AD0/SDO_9") (pintype "bidirectional"))
      (node (ref "X5") (pin "2") (pinfunction "S_2") (pintype "passive"))
    )
    (net (code "19") (name "MPU_MOSI") (class "Default")
      (node (ref "U2") (pin "36") (pinfunction "PB15_36") (pintype "bidirectional"))
      (node (ref "U3") (pin "24") (pinfunction "SDA/SDI_24") (pintype "bidirectional"))
      (node (ref "X5") (pin "3") (pinfunction "S_3") (pintype "passive"))
    )
    (net (code "20") (name "MPU_SCLK") (class "Default")
      (node (ref "U2") (pin "34") (pinfunction "PB13_34") (pintype "bidirectional"))
      (node (ref "U3") (pin "23") (pinfunction "SCL/SCLK_23") (pintype "bidirectional"))
      (node (ref "X5") (pin "4") (pinfunction "S_4") (pintype "passive"))
    )
    (net (code "21") (name "MS56_CS") (class "Default")
      (node (ref "U$2") (pin "P$4") (pinfunction "CSB_P$4") (pintype "bidirectional"))
      (node (ref "U$2") (pin "P$5") (pinfunction "CSB_P$5") (pintype "bidirectional"))
      (node (ref "U2") (pin "20") (pinfunction "PA4_20") (pintype "bidirectional"))
    )
    (net (code "22") (name "MS56_MISO") (class "Default")
      (node (ref "U$2") (pin "P$6") (pinfunction "SDO_P$6") (pintype "bidirectional"))
      (node (ref "U2") (pin "22") (pinfunction "PA6_22") (pintype "bidirectional"))
      (node (ref "X4") (pin "3") (pinfunction "S_3") (pintype "passive"))
    )
    (net (code "23") (name "MS56_MOSI") (class "Default")
      (node (ref "U$2") (pin "P$7") (pinfunction "SDI/SDA_P$7") (pintype "bidirectional"))
      (node (ref "U2") (pin "23") (pinfunction "PA7_23") (pintype "bidirectional"))
      (node (ref "X4") (pin "2") (pinfunction "S_2") (pintype "passive"))
    )
    (net (code "24") (name "MS56_SCLK") (class "Default")
      (node (ref "U$2") (pin "P$8") (pinfunction "SCLK_P$8") (pintype "bidirectional"))
      (node (ref "U2") (pin "21") (pinfunction "PA5_21") (pintype "bidirectional"))
      (node (ref "X4") (pin "4") (pinfunction "S_4") (pintype "passive"))
    )
    (net (code "25") (name "NRST") (class "Default")
      (node (ref "C10") (pin "1") (pinfunction "1_1") (pintype "passive"))
      (node (ref "S1") (pin "1") (pinfunction "1_1") (pintype "passive"))
      (node (ref "S1") (pin "4") (pinfunction "1_4") (pintype "passive"))
      (node (ref "U2") (pin "7") (pinfunction "NRST_7") (pintype "bidirectional"))
      (node (ref "X1") (pin "2") (pinfunction "S_2") (pintype "passive"))
    )
    (net (code "26") (name "Net-(LED1-PadA)") (class "Default")
      (node (ref "LED1") (pin "A") (pinfunction "A_A") (pintype "passive"))
      (node (ref "R14") (pin "1") (pinfunction "1_1") (pintype "passive"))
    )
    (net (code "27") (name "Net-(LED2-PadA)") (class "Default")
      (node (ref "LED2") (pin "A") (pinfunction "A_A") (pintype "passive"))
      (node (ref "R15") (pin "2") (pinfunction "2_2") (pintype "passive"))
    )
    (net (code "28") (name "Net-(LED3-PadC)") (class "Default")
      (node (ref "LED3") (pin "C") (pinfunction "C_C") (pintype "passive"))
      (node (ref "R21") (pin "2") (pinfunction "2_2") (pintype "passive"))
    )
    (net (code "29") (name "Net-(LED4-PadC)") (class "Default")
      (node (ref "LED4") (pin "C") (pinfunction "C_C") (pintype "passive"))
      (node (ref "R5") (pin "2") (pinfunction "2_2") (pintype "passive"))
    )
    (net (code "30") (name "Net-(LED6-PadA)") (class "Default")
      (node (ref "LED6") (pin "A") (pinfunction "A_A") (pintype "passive"))
      (node (ref "R1") (pin "1") (pinfunction "1_1") (pintype "passive"))
    )
    (net (code "31") (name "Net-(LED7-PadA)") (class "Default")
      (node (ref "LED7") (pin "A") (pinfunction "A_A") (pintype "passive"))
      (node (ref "R27") (pin "1") (pinfunction "1_1") (pintype "passive"))
    )
    (net (code "32") (name "Net-(LED8-PadA)") (class "Default")
      (node (ref "LED8") (pin "A") (pinfunction "A_A") (pintype "passive"))
      (node (ref "R28") (pin "1") (pinfunction "1_1") (pintype "passive"))
    )
    (net (code "33") (name "Net-(LED9-PadA)") (class "Default")
      (node (ref "LED9") (pin "A") (pinfunction "A_A") (pintype "passive"))
      (node (ref "R29") (pin "1") (pinfunction "1_1") (pintype "passive"))
    )
    (net (code "34") (name "Net-(Q1-2)") (class "Default")
      (node (ref "C8") (pin "2") (pinfunction "2_2") (pintype "passive"))
      (node (ref "Q1") (pin "3") (pinfunction "2_3") (pintype "passive"))
      (node (ref "U2") (pin "5") (pinfunction "PH0-OSC_IN_5") (pintype "bidirectional"))
    )
    (net (code "35") (name "Net-(Q2-B)") (class "Default")
      (node (ref "Q2") (pin "1") (pinfunction "B_1") (pintype "passive"))
      (node (ref "R22") (pin "2") (pinfunction "2_2") (pintype "passive"))
    )
    (net (code "36") (name "Net-(R3-Pad2)") (class "Default")
      (node (ref "R3") (pin "2") (pinfunction "2_2") (pintype "passive"))
      (node (ref "R4") (pin "2") (pinfunction "2_2") (pintype "passive"))
      (node (ref "T1") (pin "B") (pinfunction "B_B") (pintype "passive"))
    )
    (net (code "37") (name "Net-(R6-Pad2)") (class "Default")
      (node (ref "R6") (pin "2") (pinfunction "2_2") (pintype "passive"))
      (node (ref "X6") (pin "7") (pinfunction "7_7") (pintype "passive"))
    )
    (net (code "38") (name "Net-(R7-Pad2)") (class "Default")
      (node (ref "R7") (pin "2") (pinfunction "2_2") (pintype "passive"))
      (node (ref "X6") (pin "8") (pinfunction "8_8") (pintype "passive"))
    )
    (net (code "39") (name "Net-(R12-Pad2)") (class "Default")
      (node (ref "R12") (pin "2") (pinfunction "2_2") (pintype "passive"))
      (node (ref "R13") (pin "2") (pinfunction "2_2") (pintype "passive"))
      (node (ref "T2") (pin "B") (pinfunction "B_B") (pintype "passive"))
    )
    (net (code "40") (name "Net-(R22-Pad1)") (class "Default")
      (node (ref "R22") (pin "1") (pinfunction "1_1") (pintype "passive"))
      (node (ref "R23") (pin "2") (pinfunction "2_2") (pintype "passive"))
      (node (ref "T4") (pin "C") (pinfunction "C_C") (pintype "passive"))
    )
    (net (code "41") (name "Net-(R24-Pad2)") (class "Default")
      (node (ref "R24") (pin "2") (pinfunction "2_2") (pintype "passive"))
      (node (ref "R25") (pin "2") (pinfunction "2_2") (pintype "passive"))
      (node (ref "T4") (pin "B") (pinfunction "B_B") (pintype "passive"))
    )
    (net (code "42") (name "Net-(U$1-DIO5)") (class "Default")
      (node (ref "R15") (pin "1") (pinfunction "1_1") (pintype "passive"))
      (node (ref "U$1") (pin "15") (pinfunction "DIO5_15") (pintype "bidirectional"))
    )
    (net (code "43") (name "Net-(U$1-RESET)") (class "Default")
      (node (ref "C11") (pin "1") (pinfunction "1_1") (pintype "passive"))
      (node (ref "S2") (pin "1") (pinfunction "1_1") (pintype "passive"))
      (node (ref "S2") (pin "4") (pinfunction "1_4") (pintype "passive"))
      (node (ref "U$1") (pin "5") (pinfunction "RESET_5") (pintype "input"))
    )
    (net (code "44") (name "Net-(U$1-RSSI)") (class "Default")
      (node (ref "R14") (pin "2") (pinfunction "2_2") (pintype "passive"))
      (node (ref "U$1") (pin "6") (pinfunction "RSSI_6") (pintype "bidirectional"))
    )
    (net (code "45") (name "Net-(U$3-K)") (class "Default")
      (node (ref "D2") (pin "A") (pinfunction "A_A") (pintype "passive"))
      (node (ref "U$3") (pin "P$1") (pinfunction "K_P$1") (pintype "passive"))
    )
    (net (code "46") (name "Net-(U2-BOOT0)") (class "Default")
      (node (ref "R20") (pin "2") (pinfunction "2_2") (pintype "passive"))
      (node (ref "U2") (pin "60") (pinfunction "BOOT0_60") (pintype "input"))
    )
    (net (code "47") (name "Net-(U2-PB3)") (class "Default")
      (node (ref "R27") (pin "2") (pinfunction "2_2") (pintype "passive"))
      (node (ref "U2") (pin "55") (pinfunction "PB3_55") (pintype "bidirectional"))
    )
    (net (code "48") (name "Net-(U2-PB5)") (class "Default")
      (node (ref "R28") (pin "2") (pinfunction "2_2") (pintype "passive"))
      (node (ref "U2") (pin "57") (pinfunction "PB5_57") (pintype "bidirectional"))
    )
    (net (code "49") (name "Net-(U2-PB7)") (class "Default")
      (node (ref "R29") (pin "2") (pinfunction "2_2") (pintype "passive"))
      (node (ref "U2") (pin "59") (pinfunction "PB7_59") (pintype "bidirectional"))
    )
    (net (code "50") (name "Net-(U2-PH1-OSC_OUT)") (class "Default")
      (node (ref "C9") (pin "2") (pinfunction "2_2") (pintype "passive"))
      (node (ref "Q1") (pin "1") (pinfunction "1_1") (pintype "passive"))
      (node (ref "U2") (pin "6") (pinfunction "PH1-OSC_OUT_6") (pintype "bidirectional"))
    )
    (net (code "51") (name "Net-(U2-VBAT)") (class "Default")
      (node (ref "C3") (pin "1") (pinfunction "1_1") (pintype "passive"))
      (node (ref "U2") (pin "1") (pinfunction "VBAT_1") (pintype "power_in"))
    )
    (net (code "52") (name "Net-(U2-VCAP_1)") (class "Default")
      (node (ref "C2") (pin "1") (pinfunction "1_1") (pintype "passive"))
      (node (ref "U2") (pin "30") (pinfunction "VCAP_1_30") (pintype "power_in"))
    )
    (net (code "53") (name "Net-(U3-REGOUT)") (class "Default")
      (node (ref "C22") (pin "1") (pinfunction "1_1") (pintype "passive"))
      (node (ref "U3") (pin "10") (pinfunction "REGOUT_10") (pintype "bidirectional"))
    )
    (net (code "54") (name "Net-(U17-+IN)") (class "Default")
      (node (ref "C25") (pin "2") (pinfunction "2_2") (pintype "passive"))
      (node (ref "C27") (pin "1") (pinfunction "1_1") (pintype "passive"))
      (node (ref "R8") (pin "2") (pinfunction "2_2") (pintype "passive"))
      (node (ref "U17") (pin "4") (pinfunction "+IN_4") (pintype "input"))
    )
    (net (code "55") (name "Net-(U17--IN)") (class "Default")
      (node (ref "C25") (pin "1") (pinfunction "1_1") (pintype "passive"))
      (node (ref "C26") (pin "2") (pinfunction "2_2") (pintype "passive"))
      (node (ref "R9") (pin "2") (pinfunction "2_2") (pintype "passive"))
      (node (ref "U17") (pin "1") (pinfunction "-IN_1") (pintype "input"))
    )
    (net (code "56") (name "Net-(U17-RG)") (class "Default")
      (node (ref "R10") (pin "1") (pinfunction "1_1") (pintype "passive"))
      (node (ref "U17") (pin "3") (pinfunction "RG_3") (pintype "passive"))
    )
    (net (code "57") (name "Net-(U17-RG_2)") (class "Default")
      (node (ref "R10") (pin "2") (pinfunction "2_2") (pintype "passive"))
      (node (ref "U17") (pin "2") (pinfunction "RG_2_2") (pintype "passive"))
    )
    (net (code "58") (name "Net-(U17-VOUT)") (class "Default")
      (node (ref "R11") (pin "1") (pinfunction "1_1") (pintype "passive"))
      (node (ref "U17") (pin "7") (pinfunction "VOUT_7") (pintype "output"))
    )
    (net (code "59") (name "SDIO_CK") (class "Default")
      (node (ref "J1") (pin "5") (pinfunction "CLK_5") (pintype "passive"))
      (node (ref "U2") (pin "28") (pinfunction "PB2_28") (pintype "bidirectional"))
    )
    (net (code "60") (name "SDIO_CMD") (class "Default")
      (node (ref "J1") (pin "3") (pinfunction "CMD_3") (pintype "passive"))
      (node (ref "U2") (pin "54") (pinfunction "PD2_54") (pintype "bidirectional"))
    )
    (net (code "61") (name "SDIO_D0") (class "Default")
      (node (ref "J1") (pin "7") (pinfunction "DAT0_7") (pintype "passive"))
      (node (ref "U2") (pin "39") (pinfunction "PC8_39") (pintype "bidirectional"))
    )
    (net (code "62") (name "SDIO_D1") (class "Default")
      (node (ref "J1") (pin "8") (pinfunction "DAT1_8") (pintype "passive"))
      (node (ref "U2") (pin "26") (pinfunction "PB0_26") (pintype "bidirectional"))
    )
    (net (code "63") (name "SDIO_D2") (class "Default")
      (node (ref "J1") (pin "1") (pinfunction "DAT2_1") (pintype "passive"))
      (node (ref "U2") (pin "27") (pinfunction "PB1_27") (pintype "bidirectional"))
    )
    (net (code "64") (name "SDIO_D3") (class "Default")
      (node (ref "J1") (pin "2") (pinfunction "CD/DAT3_2") (pintype "passive"))
      (node (ref "U2") (pin "52") (pinfunction "PC11_52") (pintype "bidirectional"))
    )
    (net (code "65") (name "SERVO1_PWM") (class "Default")
      (node (ref "U2") (pin "56") (pinfunction "PB4_56") (pintype "bidirectional"))
    )
    (net (code "66") (name "SERVO2_PWM") (class "Default")
      (node (ref "R6") (pin "1") (pinfunction "1_1") (pintype "passive"))
      (node (ref "U2") (pin "61") (pinfunction "PB8_61") (pintype "bidirectional"))
    )
    (net (code "67") (name "SERVO3_PWM") (class "Default")
      (node (ref "R7") (pin "1") (pinfunction "1_1") (pintype "passive"))
      (node (ref "U2") (pin "62") (pinfunction "PB9_62") (pintype "bidirectional"))
    )
    (net (code "68") (name "SWCLK") (class "Default")
      (node (ref "U2") (pin "49") (pinfunction "PA14_49") (pintype "bidirectional"))
      (node (ref "X1") (pin "3") (pinfunction "S_3") (pintype "passive"))
    )
    (net (code "69") (name "SWDIO") (class "Default")
      (node (ref "U2") (pin "46") (pinfunction "PA13_46") (pintype "bidirectional"))
      (node (ref "X1") (pin "4") (pinfunction "S_4") (pintype "passive"))
    )
    (net (code "70") (name "TENSO_ADC") (class "Default")
      (node (ref "C28") (pin "1") (pinfunction "1_1") (pintype "passive"))
      (node (ref "R11") (pin "2") (pinfunction "2_2") (pintype "passive"))
      (node (ref "U2") (pin "8") (pinfunction "PC0_8") (pintype "bidirectional"))
    )
    (net (code "71") (name "TENSO_IN+") (class "Default")
      (node (ref "R8") (pin "1") (pinfunction "1_1") (pintype "passive"))
      (node (ref "X6") (pin "14") (pinfunction "14_14") (pintype "passive"))
    )
    (net (code "72") (name "TENSO_IN-") (class "Default")
      (node (ref "R9") (pin "1") (pinfunction "1_1") (pintype "passive"))
      (node (ref "X6") (pin "15") (pinfunction "15_15") (pintype "passive"))
    )
    (net (code "73") (name "UART_RX") (class "Default")
      (node (ref "U2") (pin "17") (pinfunction "PA3_17") (pintype "bidirectional"))
      (node (ref "X2") (pin "2") (pinfunction "S_2") (pintype "passive"))
    )
    (net (code "74") (name "UART_TX") (class "Default")
      (node (ref "U2") (pin "16") (pinfunction "PA2_16") (pintype "bidirectional"))
      (node (ref "X2") (pin "3") (pinfunction "S_3") (pintype "passive"))
    )
    (net (code "75") (name "XBEE_RX") (class "Default")
      (node (ref "U$1") (pin "2") (pinfunction "DOUT_2") (pintype "output"))
      (node (ref "U2") (pin "43") (pinfunction "PA10_43") (pintype "bidirectional"))
    )
    (net (code "76") (name "XBEE_TX") (class "Default")
      (node (ref "U$1") (pin "3") (pinfunction "DIN_3") (pintype "input"))
      (node (ref "U2") (pin "42") (pinfunction "PA9_42") (pintype "bidirectional"))
    )
    (net (code "77") (name "XBEE_VDD") (class "Default")
      (node (ref "C13") (pin "+") (pinfunction "+_+") (pintype "passive"))
      (node (ref "C30") (pin "1") (pinfunction "1_1") (pintype "passive"))
      (node (ref "IC1") (pin "2") (pinfunction "OUT_2") (pintype "passive"))
      (node (ref "U$1") (pin "1") (pinfunction "VDD_1") (pintype "power_in"))
    )
    (net (code "78") (name "unconnected-(U$1-CTS-Pad12)") (class "Default")
      (node (ref "U$1") (pin "12") (pinfunction "CTS_12") (pintype "output"))
    )
    (net (code "79") (name "unconnected-(U$1-DIO0-Pad20)") (class "Default")
      (node (ref "U$1") (pin "20") (pinfunction "DIO0_20") (pintype "bidirectional"))
    )
    (net (code "80") (name "unconnected-(U$1-DIO1-Pad19)") (class "Default")
      (node (ref "U$1") (pin "19") (pinfunction "DIO1_19") (pintype "bidirectional"))
    )
    (net (code "81") (name "unconnected-(U$1-DIO2-Pad18)") (class "Default")
      (node (ref "U$1") (pin "18") (pinfunction "DIO2_18") (pintype "bidirectional"))
    )
    (net (code "82") (name "unconnected-(U$1-DIO3-Pad17)") (class "Default")
      (node (ref "U$1") (pin "17") (pinfunction "DIO3_17") (pintype "bidirectional"))
    )
    (net (code "83") (name "unconnected-(U$1-DIO4-Pad11)") (class "Default")
      (node (ref "U$1") (pin "11") (pinfunction "DIO4_11") (pintype "bidirectional"))
    )
    (net (code "84") (name "unconnected-(U$1-DIO9-Pad13)") (class "Default")
      (node (ref "U$1") (pin "13") (pinfunction "DIO9_13") (pintype "bidirectional"))
    )
    (net (code "85") (name "unconnected-(U$1-DIO11-Pad7)") (class "Default")
      (node (ref "U$1") (pin "7") (pinfunction "DIO11_7") (pintype "bidirectional"))
    )
    (net (code "86") (name "unconnected-(U$1-DIO12-Pad4)") (class "Default")
      (node (ref "U$1") (pin "4") (pinfunction "DIO12_4") (pintype "bidirectional"))
    )
    (net (code "87") (name "unconnected-(U$1-DTR-Pad9)") (class "Default")
      (node (ref "U$1") (pin "9") (pinfunction "DTR_9") (pintype "bidirectional"))
    )
    (net (code "88") (name "unconnected-(U$1-RES-Pad8)") (class "Default")
      (node (ref "U$1") (pin "8") (pinfunction "RES_8") (pintype "bidirectional"))
    )
    (net (code "89") (name "unconnected-(U$1-RES-Pad14)") (class "Default")
      (node (ref "U$1") (pin "14") (pinfunction "RES_14") (pintype "bidirectional"))
    )
    (net (code "90") (name "unconnected-(U$1-RTS-Pad16)") (class "Default")
      (node (ref "U$1") (pin "16") (pinfunction "RTS_16") (pintype "input"))
    )
    (net (code "91") (name "unconnected-(U$10-PadP$1)") (class "Default")
      (node (ref "U$10") (pin "P$1") (pinfunction "P$1_P$1") (pintype "bidirectional"))
    )
    (net (code "92") (name "unconnected-(U1-VREF-Pad5)") (class "Default")
      (node (ref "U1") (pin "5") (pinfunction "VREF_5") (pintype "output"))
    )
    (net (code "93") (name "unconnected-(U2-PA0-Pad14)") (class "Default")
      (node (ref "U2") (pin "14") (pinfunction "PA0_14") (pintype "bidirectional"))
    )
    (net (code "94") (name "unconnected-(U2-PA1-Pad15)") (class "Default")
      (node (ref "U2") (pin "15") (pinfunction "PA1_15") (pintype "bidirectional"))
    )
    (net (code "95") (name "unconnected-(U2-PA8-Pad41)") (class "Default")
      (node (ref "U2") (pin "41") (pinfunction "PA8_41") (pintype "bidirectional"))
    )
    (net (code "96") (name "unconnected-(U2-PA15-Pad50)") (class "Default")
      (node (ref "U2") (pin "50") (pinfunction "PA15_50") (pintype "bidirectional"))
    )
    (net (code "97") (name "unconnected-(U2-PB10-Pad29)") (class "Default")
      (node (ref "U2") (pin "29") (pinfunction "PB10_29") (pintype "bidirectional"))
    )
    (net (code "98") (name "unconnected-(U2-PC1-Pad9)") (class "Default")
      (node (ref "U2") (pin "9") (pinfunction "PC1_9") (pintype "bidirectional"))
    )
    (net (code "99") (name "unconnected-(U2-PC2-Pad10)") (class "Default")
      (node (ref "U2") (pin "10") (pinfunction "PC2_10") (pintype "bidirectional"))
    )
    (net (code "100") (name "unconnected-(U2-PC3-Pad11)") (class "Default")
      (node (ref "U2") (pin "11") (pinfunction "PC3_11") (pintype "bidirectional"))
    )
    (net (code "101") (name "unconnected-(U2-PC4-Pad24)") (class "Default")
      (node (ref "U2") (pin "24") (pinfunction "PC4_24") (pintype "bidirectional"))
    )
    (net (code "102") (name "unconnected-(U2-PC5-Pad25)") (class "Default")
      (node (ref "U2") (pin "25") (pinfunction "PC5_25") (pintype "bidirectional"))
    )
    (net (code "103") (name "unconnected-(U2-PC7-Pad38)") (class "Default")
      (node (ref "U2") (pin "38") (pinfunction "PC7_38") (pintype "bidirectional"))
    )
    (net (code "104") (name "unconnected-(U2-PC9-Pad40)") (class "Default")
      (node (ref "U2") (pin "40") (pinfunction "PC9_40") (pintype "bidirectional"))
    )
    (net (code "105") (name "unconnected-(U2-PC13-Pad2)") (class "Default")
      (node (ref "U2") (pin "2") (pinfunction "PC13_2") (pintype "bidirectional"))
    )
    (net (code "106") (name "unconnected-(U2-PC14-OSC32_IN-Pad3)") (class "Default")
      (node (ref "U2") (pin "3") (pinfunction "PC14-OSC32_IN_3") (pintype "bidirectional"))
    )
    (net (code "107") (name "unconnected-(U2-PC15-OSC32_OUT-Pad4)") (class "Default")
      (node (ref "U2") (pin "4") (pinfunction "PC15-OSC32_OUT_4") (pintype "bidirectional"))
    )
    (net (code "108") (name "unconnected-(U3-AUX_CL-Pad7)") (class "Default")
      (node (ref "U3") (pin "7") (pinfunction "AUX_CL_7") (pintype "bidirectional"))
    )
    (net (code "109") (name "unconnected-(U3-AUX_DA-Pad21)") (class "Default")
      (node (ref "U3") (pin "21") (pinfunction "AUX_DA_21") (pintype "bidirectional"))
    )
    (net (code "110") (name "unconnected-(U3-NC-Pad2)") (class "Default")
      (node (ref "U3") (pin "2") (pinfunction "NC_2") (pintype "bidirectional"))
    )
    (net (code "111") (name "unconnected-(U3-NC-Pad3)") (class "Default")
      (node (ref "U3") (pin "3") (pinfunction "NC_3") (pintype "bidirectional"))
    )
    (net (code "112") (name "unconnected-(U3-NC-Pad4)") (class "Default")
      (node (ref "U3") (pin "4") (pinfunction "NC_4") (pintype "bidirectional"))
    )
    (net (code "113") (name "unconnected-(U3-NC-Pad5)") (class "Default")
      (node (ref "U3") (pin "5") (pinfunction "NC_5") (pintype "bidirectional"))
    )
    (net (code "114") (name "unconnected-(U3-NC-Pad6)") (class "Default")
      (node (ref "U3") (pin "6") (pinfunction "NC_6") (pintype "bidirectional"))
    )
    (net (code "115") (name "unconnected-(U3-NC-Pad14)") (class "Default")
      (node (ref "U3") (pin "14") (pinfunction "NC_14") (pintype "bidirectional"))
    )
    (net (code "116") (name "unconnected-(U3-NC-Pad15)") (class "Default")
      (node (ref "U3") (pin "15") (pinfunction "NC_15") (pintype "bidirectional"))
    )
    (net (code "117") (name "unconnected-(U3-NC-Pad16)") (class "Default")
      (node (ref "U3") (pin "16") (pinfunction "NC_16") (pintype "bidirectional"))
    )
    (net (code "118") (name "unconnected-(U3-NC-Pad17)") (class "Default")
      (node (ref "U3") (pin "17") (pinfunction "NC_17") (pintype "bidirectional"))
    )
    (net (code "119") (name "unconnected-(U3-RESV-Pad19)") (class "Default")
      (node (ref "U3") (pin "19") (pinfunction "RESV_19") (pintype "bidirectional"))
    )
    (net (code "120") (name "unconnected-(X8D-S-Pad4)") (class "Default")
      (node (ref "X8") (pin "4") (pinfunction "S_4") (pintype "passive"))
    )
  )
)
